# OUTPUT.net
KiCad netlist of a schematic drawn in Altium Designer
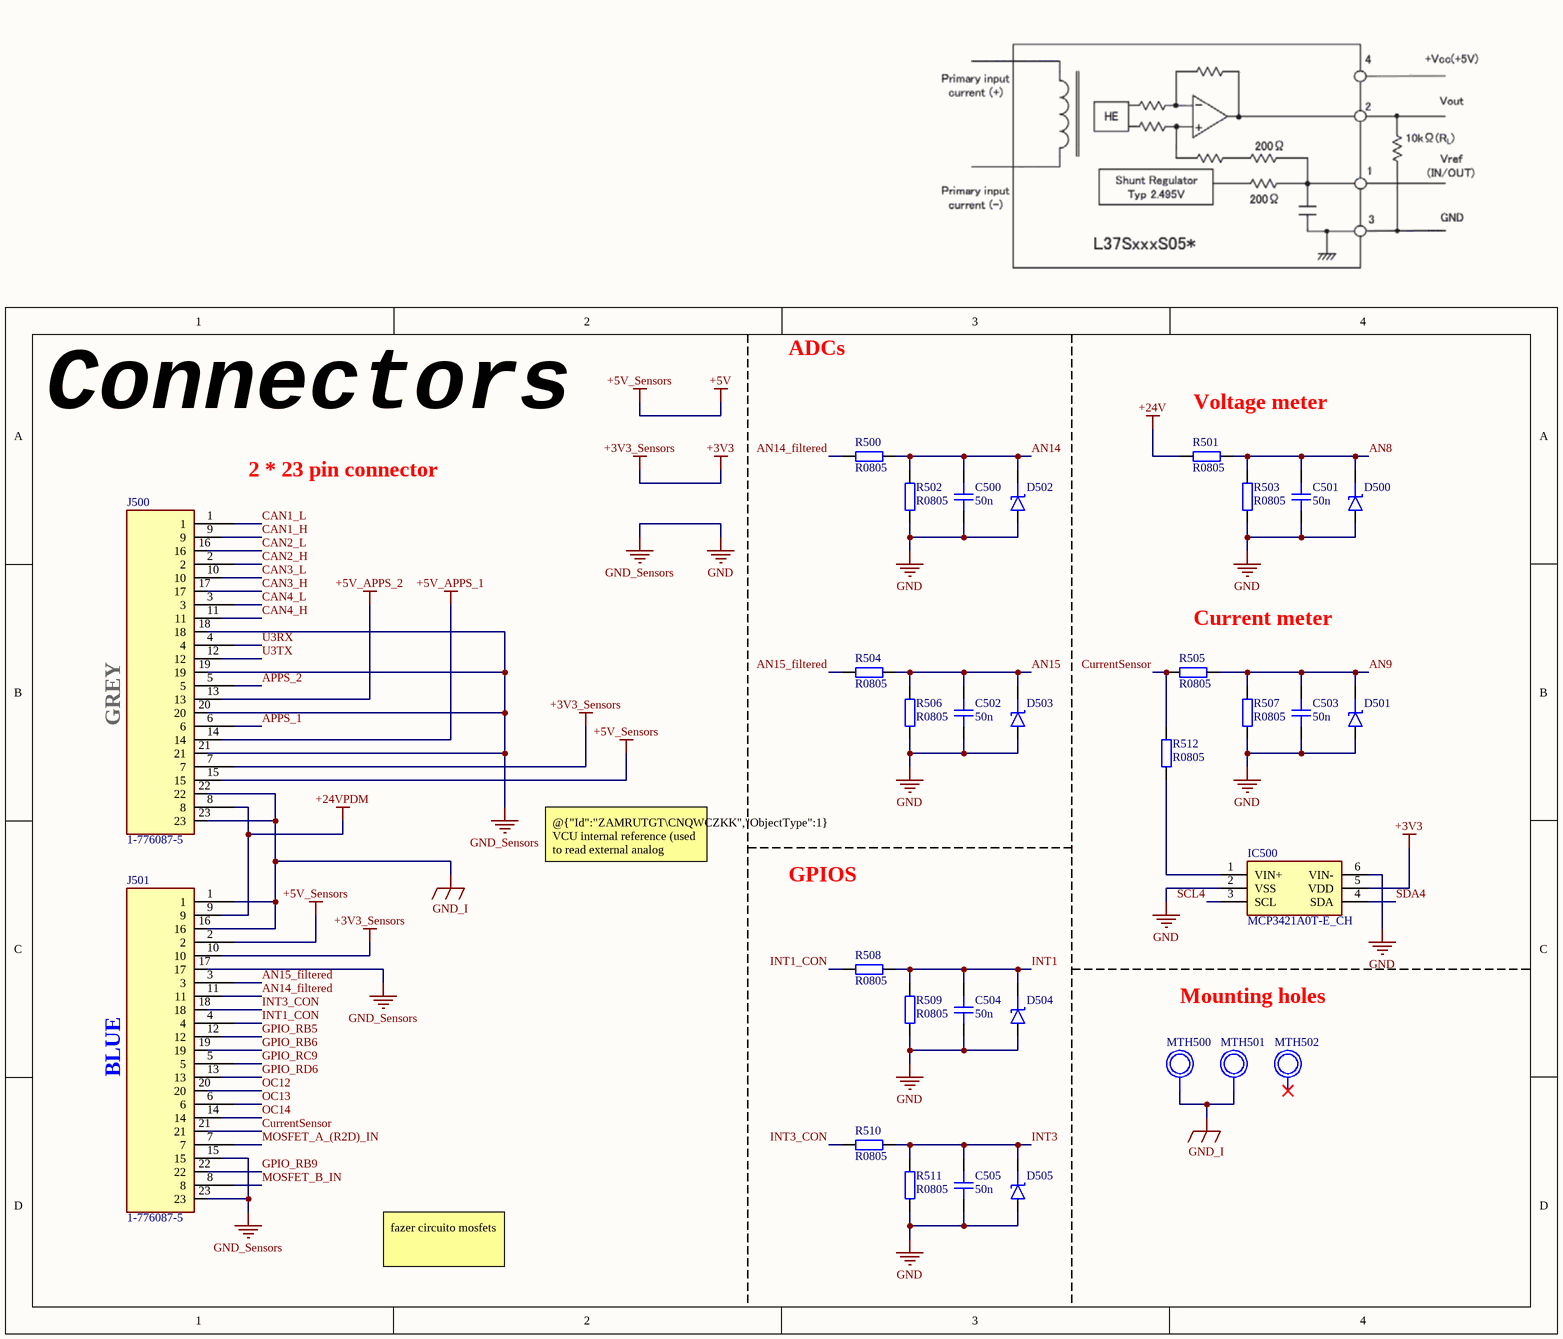
[diagram p0: OUTPUT.SchDoc]

(export (version "E")
  (design (tool "Eeschema 10.0.6"))
  (components
    (comp (ref "C500")
      (value "50n")
      (footprint "CAP_0805")
      (description "Capacitor SMD 0805 10V")
      (libsource (lib "Schematic-Lib-PhilsLab") (part "CAP_0805_10V"))
    )
    (comp (ref "C501")
      (value "50n")
      (footprint "CAP_0805")
      (description "Capacitor SMD 0805 10V")
      (libsource (lib "Schematic-Lib-PhilsLab") (part "CAP_0805_10V"))
    )
    (comp (ref "C502")
      (value "50n")
      (footprint "CAP_0805")
      (description "Capacitor SMD 0805 10V")
      (libsource (lib "Schematic-Lib-PhilsLab") (part "CAP_0805_10V"))
    )
    (comp (ref "C503")
      (value "50n")
      (footprint "CAP_0805")
      (description "Capacitor SMD 0805 10V")
      (libsource (lib "Schematic-Lib-PhilsLab") (part "CAP_0805_10V"))
    )
    (comp (ref "C504")
      (value "50n")
      (footprint "CAP_0805")
      (description "Capacitor SMD 0805 10V")
      (libsource (lib "Schematic-Lib-PhilsLab") (part "CAP_0805_10V"))
    )
    (comp (ref "C505")
      (value "50n")
      (footprint "CAP_0805")
      (description "Capacitor SMD 0805 10V")
      (libsource (lib "Schematic-Lib-PhilsLab") (part "CAP_0805_10V"))
    )
    (comp (ref "D500")
      (value "D_SCHOTTKY_SOD_323")
      (footprint "SOD-323")
      (description "Diode Schottky SMD SOD-323")
      (libsource (lib "PhilsLab") (part "D_SCHOTTKY_SOD_323"))
    )
    (comp (ref "D501")
      (value "D_SCHOTTKY_SOD_323")
      (footprint "SOD-323")
      (description "Diode Schottky SMD SOD-323")
      (libsource (lib "PhilsLab") (part "D_SCHOTTKY_SOD_323"))
    )
    (comp (ref "D502")
      (value "D_SCHOTTKY_SOD_323")
      (footprint "SOD-323")
      (description "Diode Schottky SMD SOD-323")
      (libsource (lib "PhilsLab") (part "D_SCHOTTKY_SOD_323"))
    )
    (comp (ref "D503")
      (value "D_SCHOTTKY_SOD_323")
      (footprint "SOD-323")
      (description "Diode Schottky SMD SOD-323")
      (libsource (lib "PhilsLab") (part "D_SCHOTTKY_SOD_323"))
    )
    (comp (ref "D504")
      (value "D_SCHOTTKY_SOD_323")
      (footprint "SOD-323")
      (description "Diode Schottky SMD SOD-323")
      (libsource (lib "PhilsLab") (part "D_SCHOTTKY_SOD_323"))
    )
    (comp (ref "D505")
      (value "D_SCHOTTKY_SOD_323")
      (footprint "SOD-323")
      (description "Diode Schottky SMD SOD-323")
      (libsource (lib "PhilsLab") (part "D_SCHOTTKY_SOD_323"))
    )
    (comp (ref "IC500")
      (value "MCP3421A0T-E_CH")
      (footprint "Pedro_pcb_lib:SOT95P270X145-6N")
      (description "Integrated Circuit")
      (fields
        (field (name "MANUFACTURER_PART_NUMBER") "MCP3421A0T-E/CH")
        (field (name "MOUSER PART NUMBER") "579-MCP3421A0T-E/CH")
      )
      (libsource (lib "*") (part "MCP3421A0T-E_CH"))
    )
    (comp (ref "J500")
      (value "1-776087-5")
      (footprint "1-776087-5")
      (description "CONN HDR 23POS R/A W/GASKET AU")
      (libsource (lib "Pedro_Integrated_Library") (part "1-776087-5"))
    )
    (comp (ref "J501")
      (value "1-776087-5")
      (footprint "1-776087-5")
      (description "CONN HDR 23POS R/A W/GASKET AU")
      (libsource (lib "Pedro_Integrated_Library") (part "1-776087-5"))
    )
    (comp (ref "MTH500")
      (value "Mounting_Hole_3.5mm")
      (footprint "Mounting_Hole_3.5mm")
      (libsource (lib "Pedro_Integrated_Library") (part "Mounting_Hole_3.5mm"))
    )
    (comp (ref "MTH501")
      (value "Mounting_Hole_3.5mm")
      (footprint "Mounting_Hole_3.5mm")
      (libsource (lib "Pedro_Integrated_Library") (part "Mounting_Hole_3.5mm"))
    )
    (comp (ref "MTH502")
      (value "Mounting_Hole_3.5mm")
      (footprint "Mounting_Hole_3.5mm")
      (libsource (lib "Pedro_Integrated_Library") (part "Mounting_Hole_3.5mm"))
    )
    (comp (ref "R500")
      (value "R0805")
      (footprint "RES_0805")
      (description "Resistor SMD 0805")
      (libsource (lib "Schematic-Lib-PhilsLab") (part "RES_0805"))
    )
    (comp (ref "R501")
      (value "R0805")
      (footprint "RES_0805")
      (description "Resistor SMD 0805")
      (libsource (lib "Schematic-Lib-PhilsLab") (part "RES_0805"))
    )
    (comp (ref "R502")
      (value "R0805")
      (footprint "RES_0805")
      (description "Resistor SMD 0805")
      (libsource (lib "Schematic-Lib-PhilsLab") (part "RES_0805"))
    )
    (comp (ref "R503")
      (value "R0805")
      (footprint "RES_0805")
      (description "Resistor SMD 0805")
      (libsource (lib "Schematic-Lib-PhilsLab") (part "RES_0805"))
    )
    (comp (ref "R504")
      (value "R0805")
      (footprint "RES_0805")
      (description "Resistor SMD 0805")
      (libsource (lib "Schematic-Lib-PhilsLab") (part "RES_0805"))
    )
    (comp (ref "R505")
      (value "R0805")
      (footprint "RES_0805")
      (description "Resistor SMD 0805")
      (libsource (lib "Schematic-Lib-PhilsLab") (part "RES_0805"))
    )
    (comp (ref "R506")
      (value "R0805")
      (footprint "RES_0805")
      (description "Resistor SMD 0805")
      (libsource (lib "Schematic-Lib-PhilsLab") (part "RES_0805"))
    )
    (comp (ref "R507")
      (value "R0805")
      (footprint "RES_0805")
      (description "Resistor SMD 0805")
      (libsource (lib "Schematic-Lib-PhilsLab") (part "RES_0805"))
    )
    (comp (ref "R508")
      (value "R0805")
      (footprint "RES_0805")
      (description "Resistor SMD 0805")
      (libsource (lib "Schematic-Lib-PhilsLab") (part "RES_0805"))
    )
    (comp (ref "R509")
      (value "R0805")
      (footprint "RES_0805")
      (description "Resistor SMD 0805")
      (libsource (lib "Schematic-Lib-PhilsLab") (part "RES_0805"))
    )
    (comp (ref "R510")
      (value "R0805")
      (footprint "RES_0805")
      (description "Resistor SMD 0805")
      (libsource (lib "Schematic-Lib-PhilsLab") (part "RES_0805"))
    )
    (comp (ref "R511")
      (value "R0805")
      (footprint "RES_0805")
      (description "Resistor SMD 0805")
      (libsource (lib "Schematic-Lib-PhilsLab") (part "RES_0805"))
    )
    (comp (ref "R512")
      (value "R0805")
      (footprint "RES_0805")
      (description "Resistor SMD 0805")
      (libsource (lib "Schematic-Lib-PhilsLab") (part "RES_0805"))
    )
  )
  (nets
    (net (code "1") (name "+3V3") (class "Default")
      (node (ref "IC500") (pin "5") (pinfunction "VDD_5") (pintype "passive"))
      (node (ref "J500") (pin "7") (pinfunction "7_7") (pintype "passive"))
      (node (ref "J501") (pin "10") (pinfunction "10_10") (pintype "passive"))
    )
    (net (code "2") (name "+5V") (class "Default")
      (node (ref "J500") (pin "15") (pinfunction "15_15") (pintype "passive"))
      (node (ref "J501") (pin "2") (pinfunction "2_2") (pintype "passive"))
    )
    (net (code "3") (name "+5V_APPS_1") (class "Default")
      (node (ref "J500") (pin "14") (pinfunction "14_14") (pintype "passive"))
    )
    (net (code "4") (name "+5V_APPS_2") (class "Default")
      (node (ref "J500") (pin "13") (pinfunction "13_13") (pintype "passive"))
    )
    (net (code "5") (name "+24V") (class "Default")
      (node (ref "R501") (pin "2") (pinfunction "2_2") (pintype "passive"))
    )
    (net (code "6") (name "+24VPDM") (class "Default")
      (node (ref "J500") (pin "8") (pinfunction "8_8") (pintype "passive"))
      (node (ref "J501") (pin "9") (pinfunction "9_9") (pintype "passive"))
    )
    (net (code "7") (name "/AN8") (class "Default")
      (node (ref "C501") (pin "1") (pinfunction "1_1") (pintype "passive"))
      (node (ref "D500") (pin "K") (pinfunction "K_K") (pintype "passive"))
      (node (ref "R501") (pin "1") (pinfunction "1_1") (pintype "passive"))
      (node (ref "R503") (pin "1") (pinfunction "1_1") (pintype "passive"))
    )
    (net (code "8") (name "/AN9") (class "Default")
      (node (ref "C503") (pin "1") (pinfunction "1_1") (pintype "passive"))
      (node (ref "D501") (pin "K") (pinfunction "K_K") (pintype "passive"))
      (node (ref "R505") (pin "1") (pinfunction "1_1") (pintype "passive"))
      (node (ref "R507") (pin "1") (pinfunction "1_1") (pintype "passive"))
    )
    (net (code "9") (name "/AN14") (class "Default")
      (node (ref "C500") (pin "1") (pinfunction "1_1") (pintype "passive"))
      (node (ref "D502") (pin "K") (pinfunction "K_K") (pintype "passive"))
      (node (ref "R500") (pin "1") (pinfunction "1_1") (pintype "passive"))
      (node (ref "R502") (pin "1") (pinfunction "1_1") (pintype "passive"))
    )
    (net (code "10") (name "/AN14_filtered") (class "Default")
      (node (ref "J501") (pin "11") (pinfunction "11_11") (pintype "passive"))
      (node (ref "R500") (pin "2") (pinfunction "2_2") (pintype "passive"))
    )
    (net (code "11") (name "/AN15") (class "Default")
      (node (ref "C502") (pin "1") (pinfunction "1_1") (pintype "passive"))
      (node (ref "D503") (pin "K") (pinfunction "K_K") (pintype "passive"))
      (node (ref "R504") (pin "1") (pinfunction "1_1") (pintype "passive"))
      (node (ref "R506") (pin "1") (pinfunction "1_1") (pintype "passive"))
    )
    (net (code "12") (name "/AN15_filtered") (class "Default")
      (node (ref "J501") (pin "3") (pinfunction "3_3") (pintype "passive"))
      (node (ref "R504") (pin "2") (pinfunction "2_2") (pintype "passive"))
    )
    (net (code "13") (name "/APPS_1") (class "Default")
      (node (ref "J500") (pin "6") (pinfunction "6_6") (pintype "passive"))
    )
    (net (code "14") (name "/APPS_2") (class "Default")
      (node (ref "J500") (pin "5") (pinfunction "5_5") (pintype "passive"))
    )
    (net (code "15") (name "/CAN1_H") (class "Default")
      (node (ref "J500") (pin "9") (pinfunction "9_9") (pintype "passive"))
    )
    (net (code "16") (name "/CAN1_L") (class "Default")
      (node (ref "J500") (pin "1") (pinfunction "1_1") (pintype "passive"))
    )
    (net (code "17") (name "/CAN2_H") (class "Default")
      (node (ref "J500") (pin "2") (pinfunction "2_2") (pintype "passive"))
    )
    (net (code "18") (name "/CAN2_L") (class "Default")
      (node (ref "J500") (pin "16") (pinfunction "16_16") (pintype "passive"))
    )
    (net (code "19") (name "/CAN3_H") (class "Default")
      (node (ref "J500") (pin "17") (pinfunction "17_17") (pintype "passive"))
    )
    (net (code "20") (name "/CAN3_L") (class "Default")
      (node (ref "J500") (pin "10") (pinfunction "10_10") (pintype "passive"))
    )
    (net (code "21") (name "/CAN4_H") (class "Default")
      (node (ref "J500") (pin "11") (pinfunction "11_11") (pintype "passive"))
    )
    (net (code "22") (name "/CAN4_L") (class "Default")
      (node (ref "J500") (pin "3") (pinfunction "3_3") (pintype "passive"))
    )
    (net (code "23") (name "/CurrentSensor") (class "Default")
      (node (ref "J501") (pin "21") (pinfunction "21_21") (pintype "passive"))
      (node (ref "R505") (pin "2") (pinfunction "2_2") (pintype "passive"))
      (node (ref "R512") (pin "1") (pinfunction "1_1") (pintype "passive"))
    )
    (net (code "24") (name "/GPIO_RB5") (class "Default")
      (node (ref "J501") (pin "12") (pinfunction "12_12") (pintype "passive"))
    )
    (net (code "25") (name "/GPIO_RB6") (class "Default")
      (node (ref "J501") (pin "19") (pinfunction "19_19") (pintype "passive"))
    )
    (net (code "26") (name "/GPIO_RB9") (class "Default")
      (node (ref "J501") (pin "22") (pinfunction "22_22") (pintype "passive"))
    )
    (net (code "27") (name "/GPIO_RC9") (class "Default")
      (node (ref "J501") (pin "5") (pinfunction "5_5") (pintype "passive"))
    )
    (net (code "28") (name "/GPIO_RD6") (class "Default")
      (node (ref "J501") (pin "13") (pinfunction "13_13") (pintype "passive"))
    )
    (net (code "29") (name "/INT1") (class "Default")
      (node (ref "C504") (pin "1") (pinfunction "1_1") (pintype "passive"))
      (node (ref "D504") (pin "K") (pinfunction "K_K") (pintype "passive"))
      (node (ref "R508") (pin "1") (pinfunction "1_1") (pintype "passive"))
      (node (ref "R509") (pin "1") (pinfunction "1_1") (pintype "passive"))
    )
    (net (code "30") (name "/INT1_CON") (class "Default")
      (node (ref "J501") (pin "4") (pinfunction "4_4") (pintype "passive"))
      (node (ref "R508") (pin "2") (pinfunction "2_2") (pintype "passive"))
    )
    (net (code "31") (name "/INT3") (class "Default")
      (node (ref "C505") (pin "1") (pinfunction "1_1") (pintype "passive"))
      (node (ref "D505") (pin "K") (pinfunction "K_K") (pintype "passive"))
      (node (ref "R510") (pin "1") (pinfunction "1_1") (pintype "passive"))
      (node (ref "R511") (pin "1") (pinfunction "1_1") (pintype "passive"))
    )
    (net (code "32") (name "/INT3_CON") (class "Default")
      (node (ref "J501") (pin "18") (pinfunction "18_18") (pintype "passive"))
      (node (ref "R510") (pin "2") (pinfunction "2_2") (pintype "passive"))
    )
    (net (code "33") (name "/MOSFET_A_(R2D)_IN") (class "Default")
      (node (ref "J501") (pin "7") (pinfunction "7_7") (pintype "passive"))
    )
    (net (code "34") (name "/MOSFET_B_IN") (class "Default")
      (node (ref "J501") (pin "8") (pinfunction "8_8") (pintype "passive"))
    )
    (net (code "35") (name "/OC12") (class "Default")
      (node (ref "J501") (pin "20") (pinfunction "20_20") (pintype "passive"))
    )
    (net (code "36") (name "/OC13") (class "Default")
      (node (ref "J501") (pin "6") (pinfunction "6_6") (pintype "passive"))
    )
    (net (code "37") (name "/OC14") (class "Default")
      (node (ref "J501") (pin "14") (pinfunction "14_14") (pintype "passive"))
    )
    (net (code "38") (name "/SCL4") (class "Default")
      (node (ref "IC500") (pin "3") (pinfunction "SCL_3") (pintype "passive"))
    )
    (net (code "39") (name "/SDA4") (class "Default")
      (node (ref "IC500") (pin "4") (pinfunction "SDA_4") (pintype "passive"))
    )
    (net (code "40") (name "/U3RX") (class "Default")
      (node (ref "J500") (pin "4") (pinfunction "4_4") (pintype "passive"))
    )
    (net (code "41") (name "/U3TX") (class "Default")
      (node (ref "J500") (pin "12") (pinfunction "12_12") (pintype "passive"))
    )
    (net (code "42") (name "GND") (class "Default")
      (node (ref "C500") (pin "2") (pinfunction "2_2") (pintype "passive"))
      (node (ref "C501") (pin "2") (pinfunction "2_2") (pintype "passive"))
      (node (ref "C502") (pin "2") (pinfunction "2_2") (pintype "passive"))
      (node (ref "C503") (pin "2") (pinfunction "2_2") (pintype "passive"))
      (node (ref "C504") (pin "2") (pinfunction "2_2") (pintype "passive"))
      (node (ref "C505") (pin "2") (pinfunction "2_2") (pintype "passive"))
      (node (ref "D500") (pin "A") (pinfunction "A_A") (pintype "passive"))
      (node (ref "D501") (pin "A") (pinfunction "A_A") (pintype "passive"))
      (node (ref "D502") (pin "A") (pinfunction "A_A") (pintype "passive"))
      (node (ref "D503") (pin "A") (pinfunction "A_A") (pintype "passive"))
      (node (ref "D504") (pin "A") (pinfunction "A_A") (pintype "passive"))
      (node (ref "D505") (pin "A") (pinfunction "A_A") (pintype "passive"))
      (node (ref "IC500") (pin "2") (pinfunction "VSS_2") (pintype "passive"))
      (node (ref "IC500") (pin "6") (pinfunction "VIN-_6") (pintype "passive"))
      (node (ref "J500") (pin "18") (pinfunction "18_18") (pintype "passive"))
      (node (ref "J500") (pin "19") (pinfunction "19_19") (pintype "passive"))
      (node (ref "J500") (pin "20") (pinfunction "20_20") (pintype "passive"))
      (node (ref "J500") (pin "21") (pinfunction "21_21") (pintype "passive"))
      (node (ref "J501") (pin "15") (pinfunction "15_15") (pintype "passive"))
      (node (ref "J501") (pin "17") (pinfunction "17_17") (pintype "passive"))
      (node (ref "J501") (pin "23") (pinfunction "23_23") (pintype "passive"))
      (node (ref "R502") (pin "2") (pinfunction "2_2") (pintype "passive"))
      (node (ref "R503") (pin "2") (pinfunction "2_2") (pintype "passive"))
      (node (ref "R506") (pin "2") (pinfunction "2_2") (pintype "passive"))
      (node (ref "R507") (pin "2") (pinfunction "2_2") (pintype "passive"))
      (node (ref "R509") (pin "2") (pinfunction "2_2") (pintype "passive"))
      (node (ref "R511") (pin "2") (pinfunction "2_2") (pintype "passive"))
    )
    (net (code "43") (name "GND_I") (class "Default")
      (node (ref "J500") (pin "22") (pinfunction "22_22") (pintype "passive"))
      (node (ref "J500") (pin "23") (pinfunction "23_23") (pintype "passive"))
      (node (ref "J501") (pin "1") (pinfunction "1_1") (pintype "passive"))
      (node (ref "J501") (pin "16") (pinfunction "16_16") (pintype "passive"))
      (node (ref "MTH500") (pin "1") (pinfunction "1_1") (pintype "passive"))
      (node (ref "MTH501") (pin "1") (pinfunction "1_1") (pintype "passive"))
    )
    (net (code "44") (name "Net-(IC500-VIN+)") (class "Default")
      (node (ref "IC500") (pin "1") (pinfunction "VIN+_1") (pintype "passive"))
      (node (ref "R512") (pin "2") (pinfunction "2_2") (pintype "passive"))
    )
    (net (code "45") (name "unconnected-(MTH502-Pad1)") (class "Default")
      (node (ref "MTH502") (pin "1") (pinfunction "1_1") (pintype "passive+no_connect"))
    )
  )
)
